# rw-directish-17mm-mk-1_2.net
KiCad netlist of a schematic drawn in EAGLE
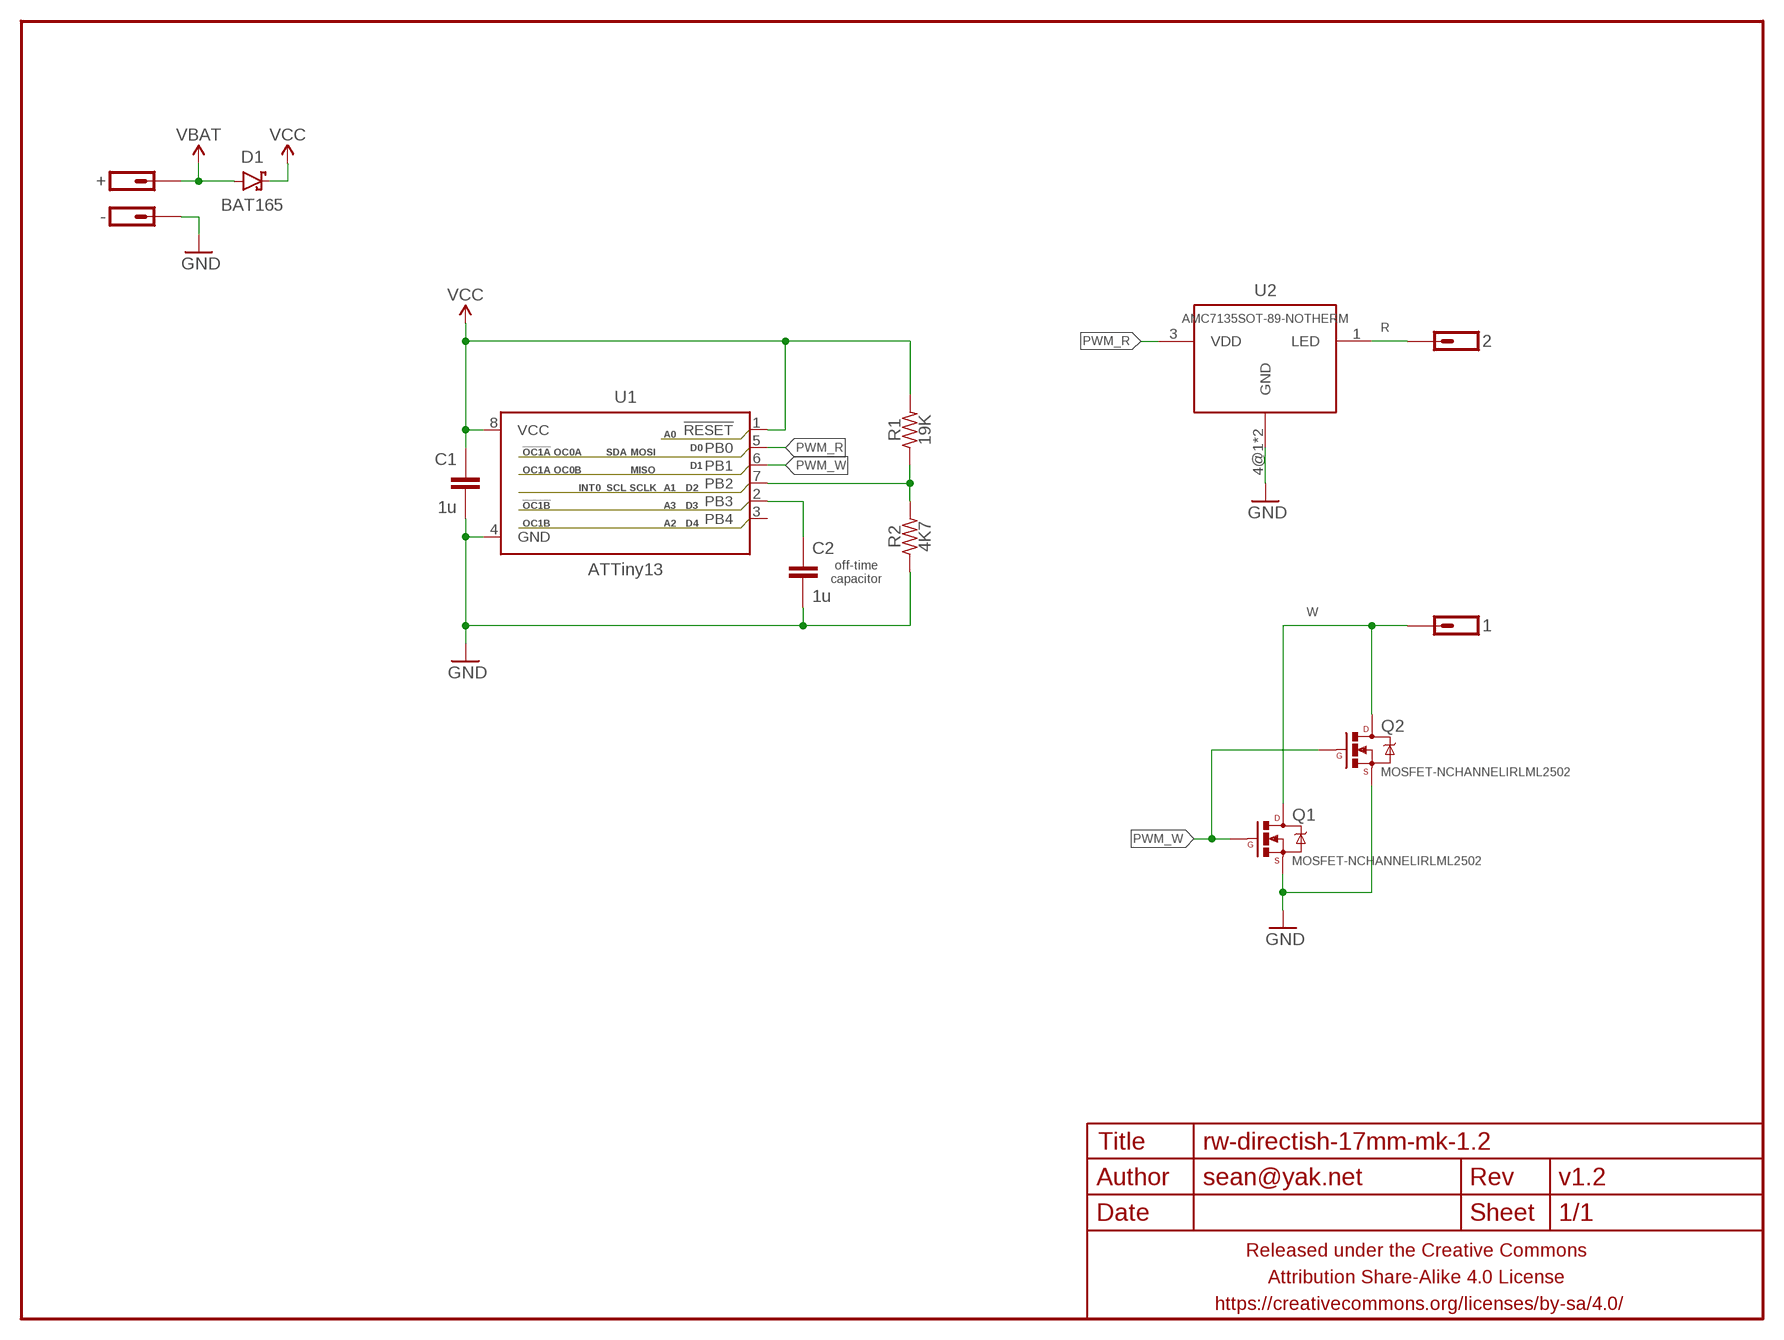
[diagram p0: schematic, sheet 1]

(export (version "E")
  (design (tool "Eeschema 10.0.6"))
  (components
    (comp (ref "+")
      (value "M01PTH-1.2MM-NS")
      (footprint "eagle-import:1X01-1.2MM-NS")
      (libsource (lib "eagle-import") (part "M01PTH-1.2MM-NS"))
    )
    (comp (ref "-")
      (value "M01NOT-A-VIA-NOPE")
      (footprint "eagle-import:1X01_NOSILK_NOSTOP")
      (libsource (lib "eagle-import") (part "M01NOT-A-VIA-NOPE"))
    )
    (comp (ref "1")
      (value "M01SMD-1.25MM-DIA")
      (footprint "eagle-import:1X01-SMD-1.25MM-DIA-NS")
      (libsource (lib "eagle-import") (part "M01SMD-1.25MM-DIA"))
    )
    (comp (ref "2")
      (value "M01SMD-1.25MM-DIA")
      (footprint "eagle-import:1X01-SMD-1.25MM-DIA-NS")
      (libsource (lib "eagle-import") (part "M01SMD-1.25MM-DIA"))
    )
    (comp (ref "C1")
      (value "1u")
      (footprint "eagle-import:C0603-TIGHTER")
      (libsource (lib "eagle-import") (part "CAPACITOR-CERAMICC0603-TIGHTER"))
    )
    (comp (ref "C2")
      (value "1u")
      (footprint "eagle-import:C0402")
      (libsource (lib "eagle-import") (part "CAPACITOR-CERAMICC0402"))
    )
    (comp (ref "D1")
      (value "BAT165")
      (footprint "eagle-import:SOD323-SCHOTTKY")
      (libsource (lib "eagle-import") (part "DIODE-SCHOTTKYSOD323"))
    )
    (comp (ref "FRAME1")
      (value "FRAME-LETTERNO_PACKAGE")
      (footprint "eagle-import:DUMMY")
      (fields (field (name "DESIGNER") "sean@yak.net") (field (name "VERSION") "v1.2"))
      (libsource (lib "eagle-import") (part "FRAME-LETTERNO_PACKAGE"))
    )
    (comp (ref "Q1")
      (value "MOSFET-NCHANNELIRLML2502")
      (footprint "eagle-import:SOT23")
      (libsource (lib "eagle-import") (part "MOSFET-NCHANNELIRLML2502"))
    )
    (comp (ref "Q2")
      (value "MOSFET-NCHANNELIRLML2502")
      (footprint "eagle-import:SOT23")
      (libsource (lib "eagle-import") (part "MOSFET-NCHANNELIRLML2502"))
    )
    (comp (ref "R1")
      (value "19K")
      (footprint "eagle-import:R0402")
      (libsource (lib "eagle-import") (part "RESISTORR0402"))
    )
    (comp (ref "R2")
      (value "4K7")
      (footprint "eagle-import:R0402")
      (libsource (lib "eagle-import") (part "RESISTORR0402"))
    )
    (comp (ref "U1")
      (value "ATTiny13")
      (footprint "eagle-import:SO08-NARROWER")
      (libsource (lib "eagle-import") (part "ATTINY13SOIC-NARROWPADS"))
    )
    (comp (ref "U2")
      (value "AMC7135SOT-89-NOTHERM")
      (footprint "eagle-import:SOT89-NOTHERM")
      (libsource (lib "eagle-import") (part "AMC7135SOT-89-NOTHERM"))
    )
  )
  (nets
    (net (code "1") (name "/R") (class "Default")
      (node (ref "2") (pin "P$1") (pinfunction "1_P$1") (pintype "passive"))
      (node (ref "U2") (pin "1") (pinfunction "LED_1") (pintype "bidirectional"))
    )
    (net (code "2") (name "/W") (class "Default")
      (node (ref "1") (pin "P$1") (pinfunction "1_P$1") (pintype "passive"))
      (node (ref "Q1") (pin "3") (pinfunction "D_3") (pintype "passive"))
      (node (ref "Q2") (pin "3") (pinfunction "D_3") (pintype "passive"))
    )
    (net (code "3") (name "GND") (class "Default")
      (node (ref "-") (pin "P$1") (pinfunction "1_P$1") (pintype "passive"))
      (node (ref "C1") (pin "2") (pinfunction "2_2") (pintype "passive"))
      (node (ref "C2") (pin "2") (pinfunction "2_2") (pintype "passive"))
      (node (ref "Q1") (pin "2") (pinfunction "S_2") (pintype "passive"))
      (node (ref "Q2") (pin "2") (pinfunction "S_2") (pintype "passive"))
      (node (ref "R2") (pin "1") (pinfunction "1_1") (pintype "passive"))
      (node (ref "U1") (pin "4") (pinfunction "GND_4") (pintype "bidirectional"))
      (node (ref "U2") (pin "4@1") (pinfunction "GND_4@1") (pintype "bidirectional"))
      (node (ref "U2") (pin "4@2") (pinfunction "GND_4@2") (pintype "bidirectional"))
    )
    (net (code "4") (name "Net-(U1-PB2)") (class "Default")
      (node (ref "R1") (pin "1") (pinfunction "1_1") (pintype "passive"))
      (node (ref "R2") (pin "2") (pinfunction "2_2") (pintype "passive"))
      (node (ref "U1") (pin "7") (pinfunction "PB2_7") (pintype "bidirectional"))
    )
    (net (code "5") (name "Net-(U1-PB3)") (class "Default")
      (node (ref "C2") (pin "1") (pinfunction "1_1") (pintype "passive"))
      (node (ref "U1") (pin "2") (pinfunction "PB3_2") (pintype "bidirectional"))
    )
    (net (code "6") (name "PWM_R") (class "Default")
      (node (ref "U1") (pin "5") (pinfunction "PB0_5") (pintype "bidirectional"))
      (node (ref "U2") (pin "3") (pinfunction "VDD_3") (pintype "bidirectional"))
    )
    (net (code "7") (name "PWM_W") (class "Default")
      (node (ref "Q1") (pin "1") (pinfunction "G_1") (pintype "passive"))
      (node (ref "Q2") (pin "1") (pinfunction "G_1") (pintype "passive"))
      (node (ref "U1") (pin "6") (pinfunction "PB1_6") (pintype "bidirectional"))
    )
    (net (code "8") (name "VBAT") (class "Default")
      (node (ref "+") (pin "P$1") (pinfunction "1_P$1") (pintype "passive"))
      (node (ref "D1") (pin "A") (pinfunction "A_A") (pintype "passive"))
    )
    (net (code "9") (name "VCC") (class "Default")
      (node (ref "C1") (pin "1") (pinfunction "1_1") (pintype "passive"))
      (node (ref "D1") (pin "C") (pinfunction "C_C") (pintype "passive"))
      (node (ref "R1") (pin "2") (pinfunction "2_2") (pintype "passive"))
      (node (ref "U1") (pin "1") (pinfunction "~{RESET}_1") (pintype "bidirectional"))
      (node (ref "U1") (pin "8") (pinfunction "VCC_8") (pintype "bidirectional"))
    )
    (net (code "10") (name "unconnected-(U1-PB4-Pad3)") (class "Default")
      (node (ref "U1") (pin "3") (pinfunction "PB4_3") (pintype "bidirectional"))
    )
  )
)
